# capsense_coin.net
KiCad netlist of a schematic drawn in EAGLE
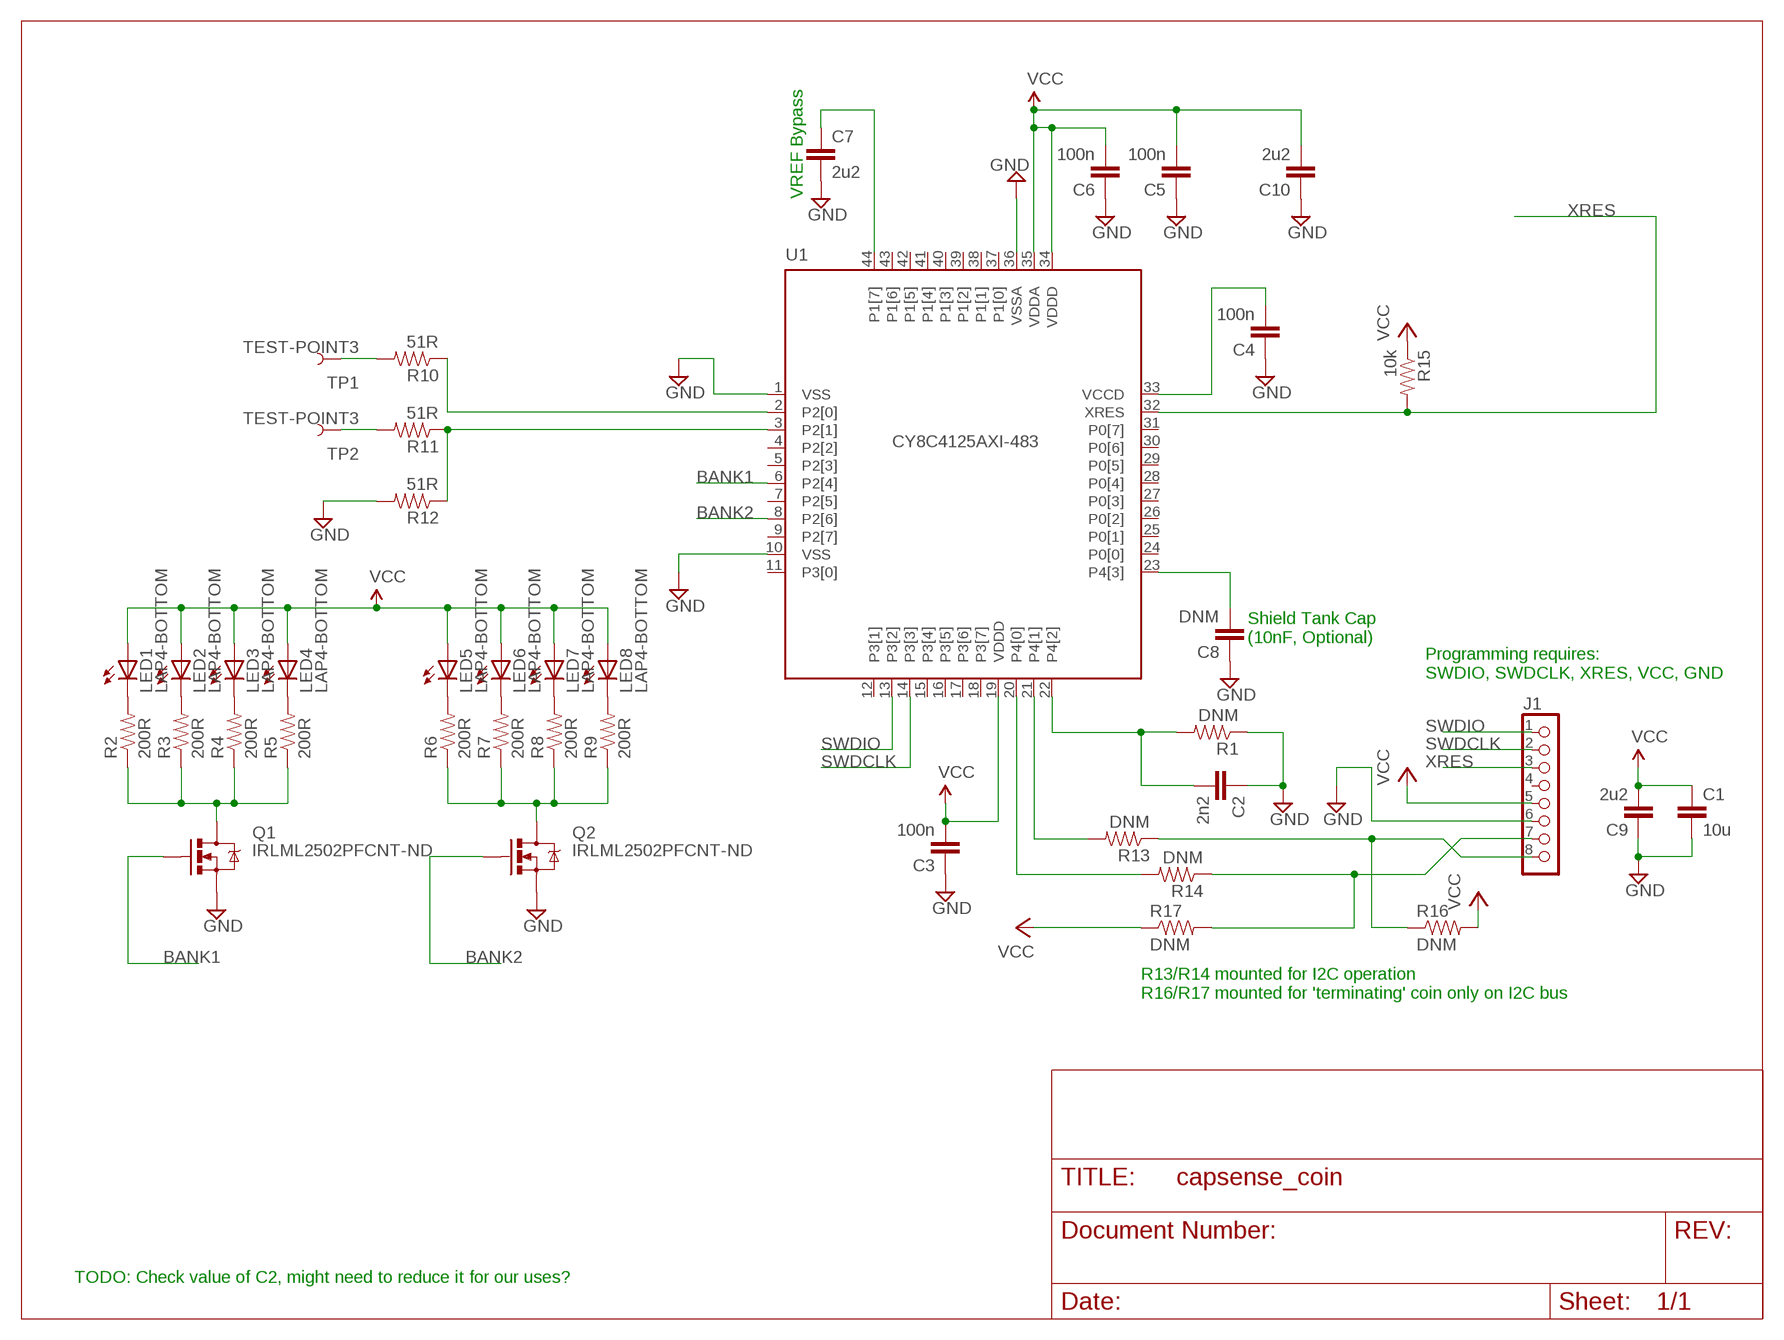
[diagram p0: schematic, sheet 1]

(export (version "E")
  (design (tool "Eeschema 10.0.6"))
  (components
    (comp (ref "C1")
      (value "10u")
      (footprint "eagle-import:0603C")
      (libsource (lib "eagle-import") (part "CAP0603-CAP"))
    )
    (comp (ref "C2")
      (value "2n2")
      (footprint "eagle-import:0603C")
      (libsource (lib "eagle-import") (part "CAP0603-CAP"))
    )
    (comp (ref "C3")
      (value "100n")
      (footprint "eagle-import:0603C")
      (libsource (lib "eagle-import") (part "CAP0603-CAP"))
    )
    (comp (ref "C4")
      (value "100n")
      (footprint "eagle-import:0603C")
      (libsource (lib "eagle-import") (part "CAP0603-CAP"))
    )
    (comp (ref "C5")
      (value "100n")
      (footprint "eagle-import:0603C")
      (libsource (lib "eagle-import") (part "CAP0603-CAP"))
    )
    (comp (ref "C6")
      (value "100n")
      (footprint "eagle-import:0603C")
      (libsource (lib "eagle-import") (part "CAP0603-CAP"))
    )
    (comp (ref "C7")
      (value "2u2")
      (footprint "eagle-import:0603C")
      (libsource (lib "eagle-import") (part "CAP0603-CAP"))
    )
    (comp (ref "C8")
      (value "DNM")
      (footprint "eagle-import:0603C")
      (libsource (lib "eagle-import") (part "CAP0603-CAP"))
    )
    (comp (ref "C9")
      (value "2u2")
      (footprint "eagle-import:0603C")
      (libsource (lib "eagle-import") (part "CAP0603-CAP"))
    )
    (comp (ref "C10")
      (value "2u2")
      (footprint "eagle-import:0603C")
      (libsource (lib "eagle-import") (part "CAP0603-CAP"))
    )
    (comp (ref "J1")
      (value "CON_HEADER_1X08")
      (footprint "eagle-import:DF13C-VERTSMD")
      (libsource (lib "eagle-import") (part "CON_HEADER_1X08"))
    )
    (comp (ref "LED1")
      (value "LAP4-BOTTOM")
      (footprint "eagle-import:P47F-BOTTOM")
      (libsource (lib "eagle-import") (part "P4-BOTTOMLA"))
    )
    (comp (ref "LED2")
      (value "LAP4-BOTTOM")
      (footprint "eagle-import:P47F-BOTTOM")
      (libsource (lib "eagle-import") (part "P4-BOTTOMLA"))
    )
    (comp (ref "LED3")
      (value "LAP4-BOTTOM")
      (footprint "eagle-import:P47F-BOTTOM")
      (libsource (lib "eagle-import") (part "P4-BOTTOMLA"))
    )
    (comp (ref "LED4")
      (value "LAP4-BOTTOM")
      (footprint "eagle-import:P47F-BOTTOM")
      (libsource (lib "eagle-import") (part "P4-BOTTOMLA"))
    )
    (comp (ref "LED5")
      (value "LAP4-BOTTOM")
      (footprint "eagle-import:P47F-BOTTOM")
      (libsource (lib "eagle-import") (part "P4-BOTTOMLA"))
    )
    (comp (ref "LED6")
      (value "LAP4-BOTTOM")
      (footprint "eagle-import:P47F-BOTTOM")
      (libsource (lib "eagle-import") (part "P4-BOTTOMLA"))
    )
    (comp (ref "LED7")
      (value "LAP4-BOTTOM")
      (footprint "eagle-import:P47F-BOTTOM")
      (libsource (lib "eagle-import") (part "P4-BOTTOMLA"))
    )
    (comp (ref "LED8")
      (value "LAP4-BOTTOM")
      (footprint "eagle-import:P47F-BOTTOM")
      (libsource (lib "eagle-import") (part "P4-BOTTOMLA"))
    )
    (comp (ref "Q1")
      (value "IRLML2502PFCNT-ND")
      (footprint "eagle-import:SOT23")
      (libsource (lib "eagle-import") (part "MOSFET-NCHANNELBSS123LT1G"))
    )
    (comp (ref "Q2")
      (value "IRLML2502PFCNT-ND")
      (footprint "eagle-import:SOT23")
      (libsource (lib "eagle-import") (part "MOSFET-NCHANNELBSS123LT1G"))
    )
    (comp (ref "R1")
      (value "DNM")
      (footprint "eagle-import:0603R")
      (libsource (lib "eagle-import") (part "RES0603-RES"))
    )
    (comp (ref "R2")
      (value "200R")
      (footprint "eagle-import:0603R")
      (libsource (lib "eagle-import") (part "RES0603-RES"))
    )
    (comp (ref "R3")
      (value "200R")
      (footprint "eagle-import:0603R")
      (libsource (lib "eagle-import") (part "RES0603-RES"))
    )
    (comp (ref "R4")
      (value "200R")
      (footprint "eagle-import:0603R")
      (libsource (lib "eagle-import") (part "RES0603-RES"))
    )
    (comp (ref "R5")
      (value "200R")
      (footprint "eagle-import:0603R")
      (libsource (lib "eagle-import") (part "RES0603-RES"))
    )
    (comp (ref "R6")
      (value "200R")
      (footprint "eagle-import:0603R")
      (libsource (lib "eagle-import") (part "RES0603-RES"))
    )
    (comp (ref "R7")
      (value "200R")
      (footprint "eagle-import:0603R")
      (libsource (lib "eagle-import") (part "RES0603-RES"))
    )
    (comp (ref "R8")
      (value "200R")
      (footprint "eagle-import:0603R")
      (libsource (lib "eagle-import") (part "RES0603-RES"))
    )
    (comp (ref "R9")
      (value "200R")
      (footprint "eagle-import:0603R")
      (libsource (lib "eagle-import") (part "RES0603-RES"))
    )
    (comp (ref "R10")
      (value "51R")
      (footprint "eagle-import:0603R")
      (libsource (lib "eagle-import") (part "RES0603-RES"))
    )
    (comp (ref "R11")
      (value "51R")
      (footprint "eagle-import:0603R")
      (libsource (lib "eagle-import") (part "RES0603-RES"))
    )
    (comp (ref "R12")
      (value "51R")
      (footprint "eagle-import:0603R")
      (libsource (lib "eagle-import") (part "RES0603-RES"))
    )
    (comp (ref "R13")
      (value "DNM")
      (footprint "eagle-import:0603R")
      (libsource (lib "eagle-import") (part "RES0603-RES"))
    )
    (comp (ref "R14")
      (value "DNM")
      (footprint "eagle-import:0603R")
      (libsource (lib "eagle-import") (part "RES0603-RES"))
    )
    (comp (ref "R15")
      (value "10k")
      (footprint "eagle-import:0603R")
      (libsource (lib "eagle-import") (part "RES0603-RES"))
    )
    (comp (ref "R16")
      (value "DNM")
      (footprint "eagle-import:0603R")
      (libsource (lib "eagle-import") (part "RES0603-RES"))
    )
    (comp (ref "R17")
      (value "DNM")
      (footprint "eagle-import:0603R")
      (libsource (lib "eagle-import") (part "RES0603-RES"))
    )
    (comp (ref "TP1")
      (value "TEST-POINT3")
      (footprint "eagle-import:PAD.03X.03")
      (libsource (lib "eagle-import") (part "TEST-POINT3"))
    )
    (comp (ref "TP2")
      (value "TEST-POINT3")
      (footprint "eagle-import:PAD.03X.03")
      (libsource (lib "eagle-import") (part "TEST-POINT3"))
    )
    (comp (ref "U1")
      (value "CY8C4125AXI-483")
      (footprint "eagle-import:TQFP44")
      (libsource (lib "eagle-import") (part "CY8C4XXXT"))
    )
  )
  (nets
    (net (code "1") (name "/BANK1") (class "Default")
      (node (ref "Q1") (pin "1") (pinfunction "G_1") (pintype "passive"))
      (node (ref "U1") (pin "6") (pinfunction "P2[4]_6") (pintype "bidirectional"))
    )
    (net (code "2") (name "/BANK2") (class "Default")
      (node (ref "Q2") (pin "1") (pinfunction "G_1") (pintype "passive"))
      (node (ref "U1") (pin "8") (pinfunction "P2[6]_8") (pintype "power_in"))
    )
    (net (code "3") (name "/P0[6]") (class "Default")
      (node (ref "U1") (pin "30") (pinfunction "P0[6]_30") (pintype "power_in"))
    )
    (net (code "4") (name "/P1[2]") (class "Default")
      (node (ref "U1") (pin "39") (pinfunction "P1[2]_39") (pintype "power_in"))
    )
    (net (code "5") (name "/P2[2]") (class "Default")
      (node (ref "U1") (pin "4") (pinfunction "P2[2]_4") (pintype "power_in"))
    )
    (net (code "6") (name "/P3[6]") (class "Default")
      (node (ref "U1") (pin "17") (pinfunction "P3[6]_17") (pintype "power_in"))
    )
    (net (code "7") (name "/SWDCLK") (class "Default")
      (node (ref "J1") (pin "2") (pinfunction "2_2") (pintype "passive"))
      (node (ref "U1") (pin "14") (pinfunction "P3[3]_14") (pintype "bidirectional"))
    )
    (net (code "8") (name "/SWDIO") (class "Default")
      (node (ref "J1") (pin "1") (pinfunction "1_1") (pintype "passive"))
      (node (ref "U1") (pin "13") (pinfunction "P3[2]_13") (pintype "bidirectional"))
    )
    (net (code "9") (name "/XRES") (class "Default")
      (node (ref "J1") (pin "3") (pinfunction "3_3") (pintype "passive"))
      (node (ref "R15") (pin "2") (pinfunction "2_2") (pintype "passive"))
      (node (ref "U1") (pin "32") (pinfunction "XRES_32") (pintype "bidirectional"))
    )
    (net (code "10") (name "GND") (class "Default")
      (node (ref "C1") (pin "2") (pinfunction "2_2") (pintype "passive"))
      (node (ref "C10") (pin "1") (pinfunction "1_1") (pintype "passive"))
      (node (ref "C2") (pin "1") (pinfunction "1_1") (pintype "passive"))
      (node (ref "C3") (pin "1") (pinfunction "1_1") (pintype "passive"))
      (node (ref "C4") (pin "1") (pinfunction "1_1") (pintype "passive"))
      (node (ref "C5") (pin "1") (pinfunction "1_1") (pintype "passive"))
      (node (ref "C6") (pin "1") (pinfunction "1_1") (pintype "passive"))
      (node (ref "C7") (pin "2") (pinfunction "2_2") (pintype "passive"))
      (node (ref "C8") (pin "1") (pinfunction "1_1") (pintype "passive"))
      (node (ref "C9") (pin "1") (pinfunction "1_1") (pintype "passive"))
      (node (ref "J1") (pin "6") (pinfunction "6_6") (pintype "passive"))
      (node (ref "Q1") (pin "2") (pinfunction "S_2") (pintype "passive"))
      (node (ref "Q2") (pin "2") (pinfunction "S_2") (pintype "passive"))
      (node (ref "R1") (pin "1") (pinfunction "1_1") (pintype "passive"))
      (node (ref "R12") (pin "2") (pinfunction "2_2") (pintype "passive"))
      (node (ref "U1") (pin "1") (pinfunction "VSS_1") (pintype "bidirectional"))
      (node (ref "U1") (pin "10") (pinfunction "VSS_10") (pintype "bidirectional"))
      (node (ref "U1") (pin "36") (pinfunction "VSSA_36") (pintype "bidirectional"))
    )
    (net (code "11") (name "Net-(J1-Pad7)") (class "Default")
      (node (ref "J1") (pin "7") (pinfunction "7_7") (pintype "passive"))
      (node (ref "R14") (pin "1") (pinfunction "1_1") (pintype "passive"))
      (node (ref "R17") (pin "2") (pinfunction "2_2") (pintype "passive"))
    )
    (net (code "12") (name "Net-(J1-Pad8)") (class "Default")
      (node (ref "J1") (pin "8") (pinfunction "8_8") (pintype "passive"))
      (node (ref "R13") (pin "1") (pinfunction "1_1") (pintype "passive"))
      (node (ref "R16") (pin "1") (pinfunction "1_1") (pintype "passive"))
    )
    (net (code "13") (name "Net-(LED1-PadC)") (class "Default")
      (node (ref "LED1") (pin "C") (pinfunction "C_C") (pintype "passive"))
      (node (ref "R2") (pin "2") (pinfunction "2_2") (pintype "passive"))
    )
    (net (code "14") (name "Net-(LED2-PadC)") (class "Default")
      (node (ref "LED2") (pin "C") (pinfunction "C_C") (pintype "passive"))
      (node (ref "R3") (pin "2") (pinfunction "2_2") (pintype "passive"))
    )
    (net (code "15") (name "Net-(LED3-PadC)") (class "Default")
      (node (ref "LED3") (pin "C") (pinfunction "C_C") (pintype "passive"))
      (node (ref "R4") (pin "2") (pinfunction "2_2") (pintype "passive"))
    )
    (net (code "16") (name "Net-(LED4-PadC)") (class "Default")
      (node (ref "LED4") (pin "C") (pinfunction "C_C") (pintype "passive"))
      (node (ref "R5") (pin "2") (pinfunction "2_2") (pintype "passive"))
    )
    (net (code "17") (name "Net-(LED5-PadC)") (class "Default")
      (node (ref "LED5") (pin "C") (pinfunction "C_C") (pintype "passive"))
      (node (ref "R6") (pin "2") (pinfunction "2_2") (pintype "passive"))
    )
    (net (code "18") (name "Net-(LED6-PadC)") (class "Default")
      (node (ref "LED6") (pin "C") (pinfunction "C_C") (pintype "passive"))
      (node (ref "R7") (pin "2") (pinfunction "2_2") (pintype "passive"))
    )
    (net (code "19") (name "Net-(LED7-PadC)") (class "Default")
      (node (ref "LED7") (pin "C") (pinfunction "C_C") (pintype "passive"))
      (node (ref "R8") (pin "2") (pinfunction "2_2") (pintype "passive"))
    )
    (net (code "20") (name "Net-(LED8-PadC)") (class "Default")
      (node (ref "LED8") (pin "C") (pinfunction "C_C") (pintype "passive"))
      (node (ref "R9") (pin "2") (pinfunction "2_2") (pintype "passive"))
    )
    (net (code "21") (name "Net-(Q1-D)") (class "Default")
      (node (ref "Q1") (pin "3") (pinfunction "D_3") (pintype "passive"))
      (node (ref "R2") (pin "1") (pinfunction "1_1") (pintype "passive"))
      (node (ref "R3") (pin "1") (pinfunction "1_1") (pintype "passive"))
      (node (ref "R4") (pin "1") (pinfunction "1_1") (pintype "passive"))
      (node (ref "R5") (pin "1") (pinfunction "1_1") (pintype "passive"))
    )
    (net (code "22") (name "Net-(Q2-D)") (class "Default")
      (node (ref "Q2") (pin "3") (pinfunction "D_3") (pintype "passive"))
      (node (ref "R6") (pin "1") (pinfunction "1_1") (pintype "passive"))
      (node (ref "R7") (pin "1") (pinfunction "1_1") (pintype "passive"))
      (node (ref "R8") (pin "1") (pinfunction "1_1") (pintype "passive"))
      (node (ref "R9") (pin "1") (pinfunction "1_1") (pintype "passive"))
    )
    (net (code "23") (name "Net-(TP1-1)") (class "Default")
      (node (ref "R10") (pin "2") (pinfunction "2_2") (pintype "passive"))
      (node (ref "TP1") (pin "P$1") (pinfunction "1_P$1") (pintype "bidirectional"))
    )
    (net (code "24") (name "Net-(TP2-1)") (class "Default")
      (node (ref "R11") (pin "2") (pinfunction "2_2") (pintype "passive"))
      (node (ref "TP2") (pin "P$1") (pinfunction "1_P$1") (pintype "bidirectional"))
    )
    (net (code "25") (name "Net-(U1-P1[7])") (class "Default")
      (node (ref "C7") (pin "1") (pinfunction "1_1") (pintype "passive"))
      (node (ref "U1") (pin "44") (pinfunction "P1[7]_44") (pintype "bidirectional"))
    )
    (net (code "26") (name "Net-(U1-P2[0])") (class "Default")
      (node (ref "R10") (pin "1") (pinfunction "1_1") (pintype "passive"))
      (node (ref "U1") (pin "2") (pinfunction "P2[0]_2") (pintype "bidirectional"))
    )
    (net (code "27") (name "Net-(U1-P2[1])") (class "Default")
      (node (ref "R11") (pin "1") (pinfunction "1_1") (pintype "passive"))
      (node (ref "R12") (pin "1") (pinfunction "1_1") (pintype "passive"))
      (node (ref "U1") (pin "3") (pinfunction "P2[1]_3") (pintype "bidirectional"))
    )
    (net (code "28") (name "Net-(U1-P4[0])") (class "Default")
      (node (ref "R14") (pin "2") (pinfunction "2_2") (pintype "passive"))
      (node (ref "U1") (pin "20") (pinfunction "P4[0]_20") (pintype "bidirectional"))
    )
    (net (code "29") (name "Net-(U1-P4[1])") (class "Default")
      (node (ref "R13") (pin "2") (pinfunction "2_2") (pintype "passive"))
      (node (ref "U1") (pin "21") (pinfunction "P4[1]_21") (pintype "bidirectional"))
    )
    (net (code "30") (name "Net-(U1-P4[2])") (class "Default")
      (node (ref "C2") (pin "2") (pinfunction "2_2") (pintype "passive"))
      (node (ref "R1") (pin "2") (pinfunction "2_2") (pintype "passive"))
      (node (ref "U1") (pin "22") (pinfunction "P4[2]_22") (pintype "bidirectional"))
    )
    (net (code "31") (name "Net-(U1-P4[3])") (class "Default")
      (node (ref "C8") (pin "2") (pinfunction "2_2") (pintype "passive"))
      (node (ref "U1") (pin "23") (pinfunction "P4[3]_23") (pintype "bidirectional"))
    )
    (net (code "32") (name "Net-(U1-VCCD)") (class "Default")
      (node (ref "C4") (pin "2") (pinfunction "2_2") (pintype "passive"))
      (node (ref "U1") (pin "33") (pinfunction "VCCD_33") (pintype "bidirectional"))
    )
    (net (code "33") (name "VCC") (class "Default")
      (node (ref "C1") (pin "1") (pinfunction "1_1") (pintype "passive"))
      (node (ref "C10") (pin "2") (pinfunction "2_2") (pintype "passive"))
      (node (ref "C3") (pin "2") (pinfunction "2_2") (pintype "passive"))
      (node (ref "C5") (pin "2") (pinfunction "2_2") (pintype "passive"))
      (node (ref "C6") (pin "2") (pinfunction "2_2") (pintype "passive"))
      (node (ref "C9") (pin "2") (pinfunction "2_2") (pintype "passive"))
      (node (ref "J1") (pin "5") (pinfunction "5_5") (pintype "passive"))
      (node (ref "LED1") (pin "A") (pinfunction "A_A") (pintype "passive"))
      (node (ref "LED2") (pin "A") (pinfunction "A_A") (pintype "passive"))
      (node (ref "LED3") (pin "A") (pinfunction "A_A") (pintype "passive"))
      (node (ref "LED4") (pin "A") (pinfunction "A_A") (pintype "passive"))
      (node (ref "LED5") (pin "A") (pinfunction "A_A") (pintype "passive"))
      (node (ref "LED6") (pin "A") (pinfunction "A_A") (pintype "passive"))
      (node (ref "LED7") (pin "A") (pinfunction "A_A") (pintype "passive"))
      (node (ref "LED8") (pin "A") (pinfunction "A_A") (pintype "passive"))
      (node (ref "R15") (pin "1") (pinfunction "1_1") (pintype "passive"))
      (node (ref "R16") (pin "2") (pinfunction "2_2") (pintype "passive"))
      (node (ref "R17") (pin "1") (pinfunction "1_1") (pintype "passive"))
      (node (ref "U1") (pin "19") (pinfunction "VDDD_19") (pintype "bidirectional"))
      (node (ref "U1") (pin "34") (pinfunction "VDDD_34") (pintype "bidirectional"))
      (node (ref "U1") (pin "35") (pinfunction "VDDA_35") (pintype "bidirectional"))
    )
    (net (code "34") (name "unconnected-(J1-Pad4)") (class "Default")
      (node (ref "J1") (pin "4") (pinfunction "4_4") (pintype "passive"))
    )
    (net (code "35") (name "unconnected-(U1-P0[0]-Pad24)") (class "Default")
      (node (ref "U1") (pin "24") (pinfunction "P0[0]_24") (pintype "bidirectional"))
    )
    (net (code "36") (name "unconnected-(U1-P0[1]-Pad25)") (class "Default")
      (node (ref "U1") (pin "25") (pinfunction "P0[1]_25") (pintype "bidirectional"))
    )
    (net (code "37") (name "unconnected-(U1-P0[2]-Pad26)") (class "Default")
      (node (ref "U1") (pin "26") (pinfunction "P0[2]_26") (pintype "input"))
    )
    (net (code "38") (name "unconnected-(U1-P0[3]-Pad27)") (class "Default")
      (node (ref "U1") (pin "27") (pinfunction "P0[3]_27") (pintype "bidirectional"))
    )
    (net (code "39") (name "unconnected-(U1-P0[4]-Pad28)") (class "Default")
      (node (ref "U1") (pin "28") (pinfunction "P0[4]_28") (pintype "bidirectional"))
    )
    (net (code "40") (name "unconnected-(U1-P0[5]-Pad29)") (class "Default")
      (node (ref "U1") (pin "29") (pinfunction "P0[5]_29") (pintype "bidirectional"))
    )
    (net (code "41") (name "unconnected-(U1-P0[7]-Pad31)") (class "Default")
      (node (ref "U1") (pin "31") (pinfunction "P0[7]_31") (pintype "bidirectional"))
    )
    (net (code "42") (name "unconnected-(U1-P1[0]-Pad37)") (class "Default")
      (node (ref "U1") (pin "37") (pinfunction "P1[0]_37") (pintype "bidirectional"))
    )
    (net (code "43") (name "unconnected-(U1-P1[1]-Pad38)") (class "Default")
      (node (ref "U1") (pin "38") (pinfunction "P1[1]_38") (pintype "bidirectional"))
    )
    (net (code "44") (name "unconnected-(U1-P1[3]-Pad40)") (class "Default")
      (node (ref "U1") (pin "40") (pinfunction "P1[3]_40") (pintype "bidirectional"))
    )
    (net (code "45") (name "unconnected-(U1-P1[4]-Pad41)") (class "Default")
      (node (ref "U1") (pin "41") (pinfunction "P1[4]_41") (pintype "bidirectional"))
    )
    (net (code "46") (name "unconnected-(U1-P1[5]-Pad42)") (class "Default")
      (node (ref "U1") (pin "42") (pinfunction "P1[5]_42") (pintype "bidirectional"))
    )
    (net (code "47") (name "unconnected-(U1-P1[6]-Pad43)") (class "Default")
      (node (ref "U1") (pin "43") (pinfunction "P1[6]_43") (pintype "bidirectional"))
    )
    (net (code "48") (name "unconnected-(U1-P2[3]-Pad5)") (class "Default")
      (node (ref "U1") (pin "5") (pinfunction "P2[3]_5") (pintype "bidirectional"))
    )
    (net (code "49") (name "unconnected-(U1-P2[5]-Pad7)") (class "Default")
      (node (ref "U1") (pin "7") (pinfunction "P2[5]_7") (pintype "bidirectional"))
    )
    (net (code "50") (name "unconnected-(U1-P2[7]-Pad9)") (class "Default")
      (node (ref "U1") (pin "9") (pinfunction "P2[7]_9") (pintype "bidirectional"))
    )
    (net (code "51") (name "unconnected-(U1-P3[0]-Pad11)") (class "Default")
      (node (ref "U1") (pin "11") (pinfunction "P3[0]_11") (pintype "bidirectional"))
    )
    (net (code "52") (name "unconnected-(U1-P3[1]-Pad12)") (class "Default")
      (node (ref "U1") (pin "12") (pinfunction "P3[1]_12") (pintype "bidirectional"))
    )
    (net (code "53") (name "unconnected-(U1-P3[4]-Pad15)") (class "Default")
      (node (ref "U1") (pin "15") (pinfunction "P3[4]_15") (pintype "bidirectional"))
    )
    (net (code "54") (name "unconnected-(U1-P3[5]-Pad16)") (class "Default")
      (node (ref "U1") (pin "16") (pinfunction "P3[5]_16") (pintype "bidirectional"))
    )
    (net (code "55") (name "unconnected-(U1-P3[7]-Pad18)") (class "Default")
      (node (ref "U1") (pin "18") (pinfunction "P3[7]_18") (pintype "bidirectional"))
    )
  )
)
